# PowerBricksBoard1.net
KiCad netlist of a schematic drawn in EAGLE
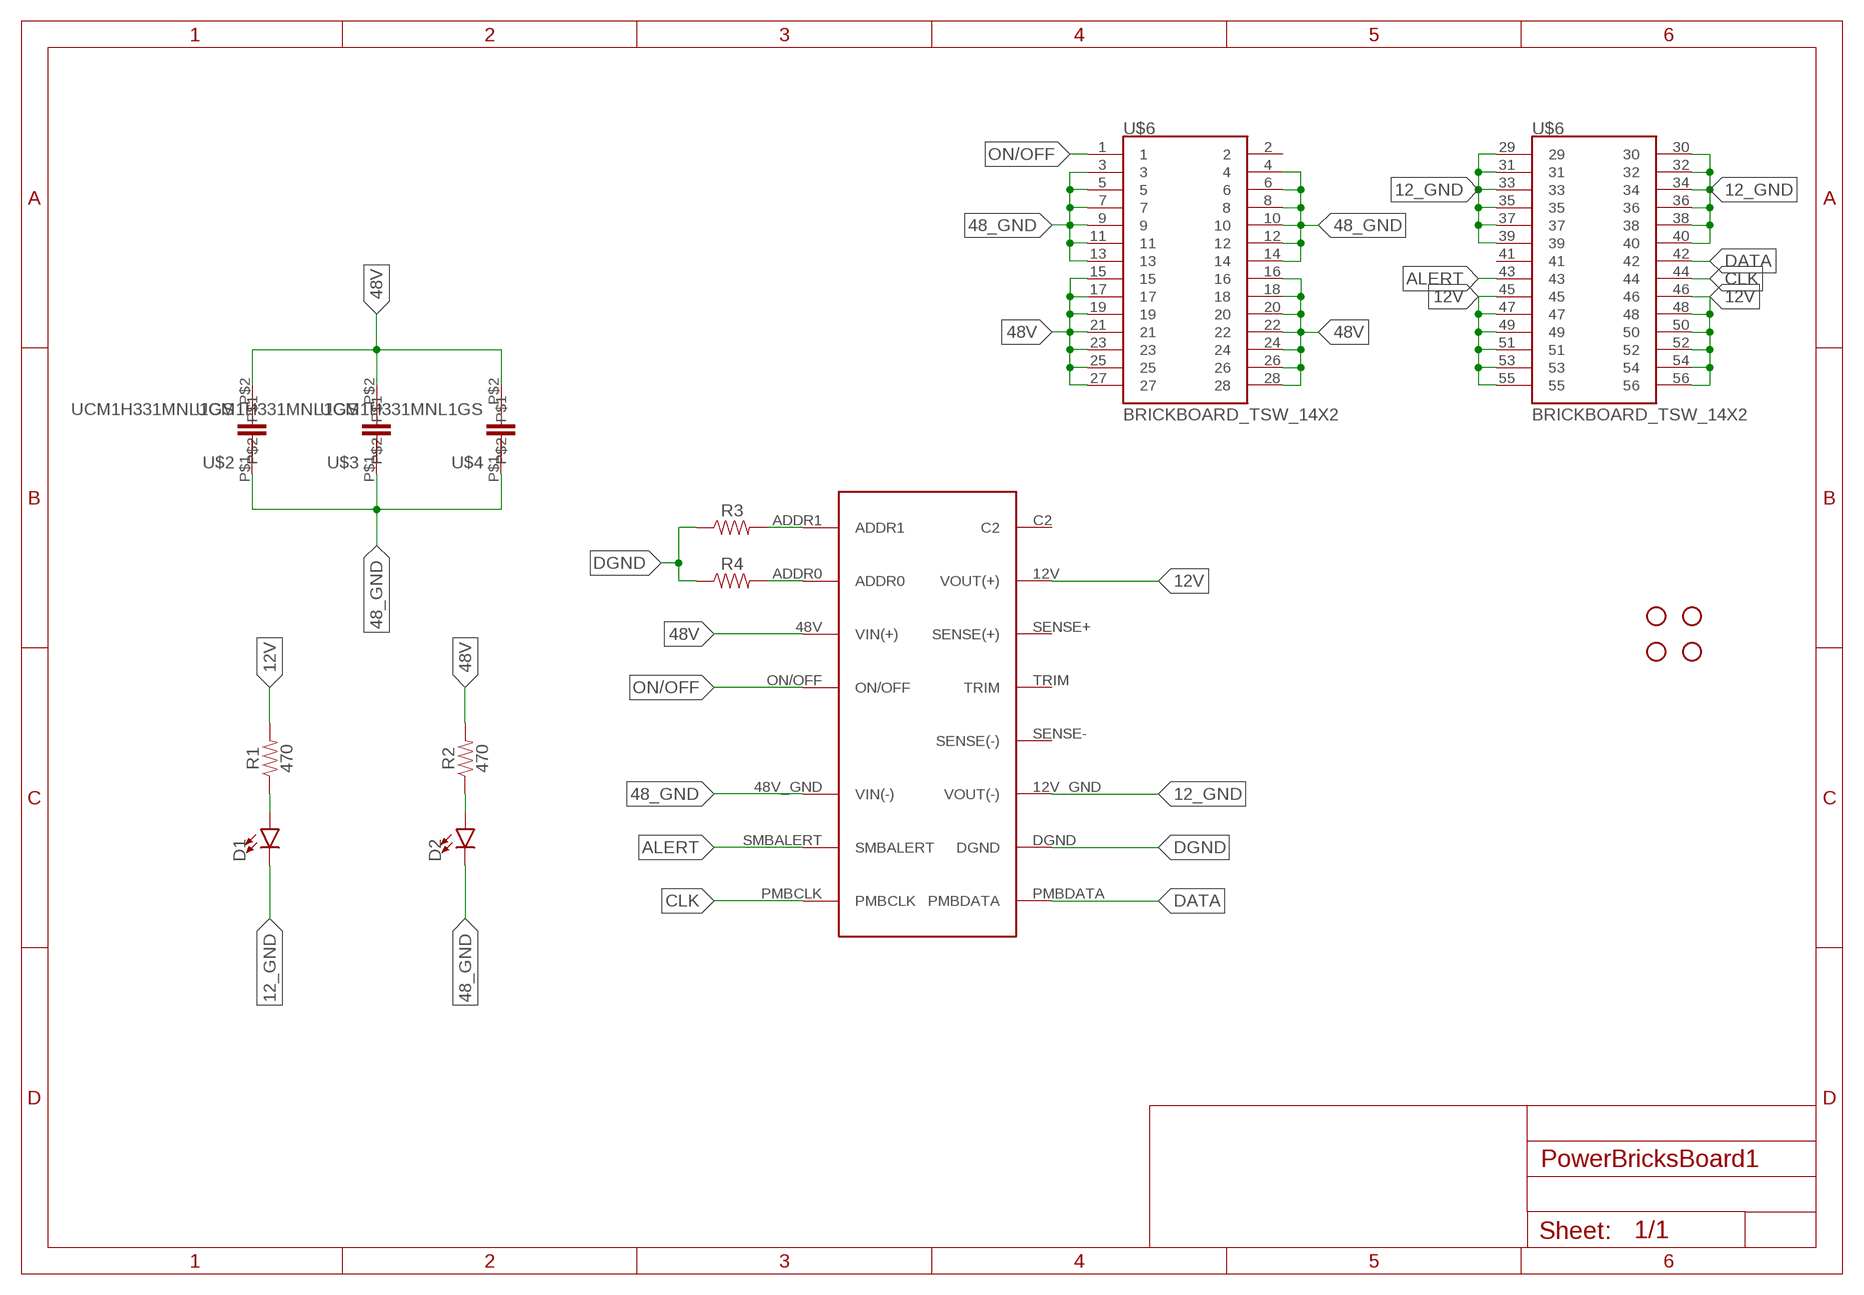
[diagram p0: schematic, sheet 1]

(export (version "E")
  (design (tool "Eeschema 10.0.6"))
  (components
    (comp (ref "D1")
      (value "LED0603")
      (footprint "eagle-import:LED-0603")
      (libsource (lib "eagle-import") (part "LED0603"))
    )
    (comp (ref "D2")
      (value "LED0603")
      (footprint "eagle-import:LED-0603")
      (libsource (lib "eagle-import") (part "LED0603"))
    )
    (comp (ref "H1")
      (value "STAND-OFF")
      (footprint "eagle-import:STAND-OFF")
      (libsource (lib "eagle-import") (part "STAND-OFF"))
    )
    (comp (ref "H2")
      (value "STAND-OFF")
      (footprint "eagle-import:STAND-OFF")
      (libsource (lib "eagle-import") (part "STAND-OFF"))
    )
    (comp (ref "H3")
      (value "STAND-OFF")
      (footprint "eagle-import:STAND-OFF")
      (libsource (lib "eagle-import") (part "STAND-OFF"))
    )
    (comp (ref "H4")
      (value "STAND-OFF")
      (footprint "eagle-import:STAND-OFF")
      (libsource (lib "eagle-import") (part "STAND-OFF"))
    )
    (comp (ref "R1")
      (value "470")
      (footprint "eagle-import:0603")
      (libsource (lib "eagle-import") (part "RESISTOR0603"))
    )
    (comp (ref "R2")
      (value "470")
      (footprint "eagle-import:0603")
      (libsource (lib "eagle-import") (part "RESISTOR0603"))
    )
    (comp (ref "R3")
      (value "RESISTOR0603")
      (footprint "eagle-import:0603")
      (libsource (lib "eagle-import") (part "RESISTOR0603"))
    )
    (comp (ref "R4")
      (value "RESISTOR0603")
      (footprint "eagle-import:0603")
      (libsource (lib "eagle-import") (part "RESISTOR0603"))
    )
    (comp (ref "U$1")
      (value "Q48SC12050NRDH")
      (footprint "eagle-import:Q48SC12050NRDH")
      (libsource (lib "eagle-import") (part "Q48SC12050NRDH"))
    )
    (comp (ref "U$2")
      (value "UCM1H331MNL1GS")
      (footprint "eagle-import:UCM1H331MNL1GS")
      (libsource (lib "eagle-import") (part "UCM1H331MNL1GS"))
    )
    (comp (ref "U$3")
      (value "UCM1H331MNL1GS")
      (footprint "eagle-import:UCM1H331MNL1GS")
      (libsource (lib "eagle-import") (part "UCM1H331MNL1GS"))
    )
    (comp (ref "U$4")
      (value "UCM1H331MNL1GS")
      (footprint "eagle-import:UCM1H331MNL1GS")
      (libsource (lib "eagle-import") (part "UCM1H331MNL1GS"))
    )
    (comp (ref "U$6")
      (value "BRICKBOARD_TSW_14X2")
      (footprint "eagle-import:BRICKBOARD_TSW_14X2")
      (libsource (lib "eagle-import") (part "BRICKBOARD_TSW_14X2"))
    )
  )
  (nets
    (net (code "1") (name "12V") (class "Default")
      (node (ref "R1") (pin "2") (pinfunction "2_2") (pintype "passive"))
      (node (ref "U$1") (pin "12V") (pinfunction "VOUT(+)_12V") (pintype "bidirectional"))
      (node (ref "U$6") (pin "45") (pinfunction "45_45") (pintype "bidirectional"))
      (node (ref "U$6") (pin "46") (pinfunction "46_46") (pintype "bidirectional"))
      (node (ref "U$6") (pin "47") (pinfunction "47_47") (pintype "bidirectional"))
      (node (ref "U$6") (pin "48") (pinfunction "48_48") (pintype "bidirectional"))
      (node (ref "U$6") (pin "49") (pinfunction "49_49") (pintype "bidirectional"))
      (node (ref "U$6") (pin "50") (pinfunction "50_50") (pintype "bidirectional"))
      (node (ref "U$6") (pin "51") (pinfunction "51_51") (pintype "bidirectional"))
      (node (ref "U$6") (pin "52") (pinfunction "52_52") (pintype "bidirectional"))
      (node (ref "U$6") (pin "53") (pinfunction "53_53") (pintype "bidirectional"))
      (node (ref "U$6") (pin "54") (pinfunction "54_54") (pintype "bidirectional"))
      (node (ref "U$6") (pin "55") (pinfunction "55_55") (pintype "bidirectional"))
      (node (ref "U$6") (pin "56") (pinfunction "56_56") (pintype "bidirectional"))
    )
    (net (code "2") (name "12_GND") (class "Default")
      (node (ref "D1") (pin "C") (pinfunction "C_C") (pintype "passive"))
      (node (ref "U$1") (pin "12V_GND") (pinfunction "VOUT(-)_12V_GND") (pintype "bidirectional"))
      (node (ref "U$6") (pin "29") (pinfunction "29_29") (pintype "bidirectional"))
      (node (ref "U$6") (pin "30") (pinfunction "30_30") (pintype "bidirectional"))
      (node (ref "U$6") (pin "31") (pinfunction "31_31") (pintype "bidirectional"))
      (node (ref "U$6") (pin "32") (pinfunction "32_32") (pintype "bidirectional"))
      (node (ref "U$6") (pin "33") (pinfunction "33_33") (pintype "bidirectional"))
      (node (ref "U$6") (pin "34") (pinfunction "34_34") (pintype "bidirectional"))
      (node (ref "U$6") (pin "35") (pinfunction "35_35") (pintype "bidirectional"))
      (node (ref "U$6") (pin "36") (pinfunction "36_36") (pintype "bidirectional"))
      (node (ref "U$6") (pin "37") (pinfunction "37_37") (pintype "bidirectional"))
      (node (ref "U$6") (pin "38") (pinfunction "38_38") (pintype "bidirectional"))
      (node (ref "U$6") (pin "39") (pinfunction "39_39") (pintype "bidirectional"))
      (node (ref "U$6") (pin "40") (pinfunction "40_40") (pintype "bidirectional"))
    )
    (net (code "3") (name "48V") (class "Default")
      (node (ref "R2") (pin "2") (pinfunction "2_2") (pintype "passive"))
      (node (ref "U$1") (pin "48V") (pinfunction "VIN(+)_48V") (pintype "bidirectional"))
      (node (ref "U$2") (pin "P$2") (pinfunction "P$2_P$2") (pintype "bidirectional"))
      (node (ref "U$3") (pin "P$2") (pinfunction "P$2_P$2") (pintype "bidirectional"))
      (node (ref "U$4") (pin "P$2") (pinfunction "P$2_P$2") (pintype "bidirectional"))
      (node (ref "U$6") (pin "15") (pinfunction "15_15") (pintype "bidirectional"))
      (node (ref "U$6") (pin "16") (pinfunction "16_16") (pintype "bidirectional"))
      (node (ref "U$6") (pin "17") (pinfunction "17_17") (pintype "bidirectional"))
      (node (ref "U$6") (pin "18") (pinfunction "18_18") (pintype "bidirectional"))
      (node (ref "U$6") (pin "19") (pinfunction "19_19") (pintype "bidirectional"))
      (node (ref "U$6") (pin "20") (pinfunction "20_20") (pintype "bidirectional"))
      (node (ref "U$6") (pin "21") (pinfunction "21_21") (pintype "bidirectional"))
      (node (ref "U$6") (pin "22") (pinfunction "22_22") (pintype "bidirectional"))
      (node (ref "U$6") (pin "23") (pinfunction "23_23") (pintype "bidirectional"))
      (node (ref "U$6") (pin "24") (pinfunction "24_24") (pintype "bidirectional"))
      (node (ref "U$6") (pin "25") (pinfunction "25_25") (pintype "bidirectional"))
      (node (ref "U$6") (pin "26") (pinfunction "26_26") (pintype "bidirectional"))
      (node (ref "U$6") (pin "27") (pinfunction "27_27") (pintype "bidirectional"))
      (node (ref "U$6") (pin "28") (pinfunction "28_28") (pintype "bidirectional"))
    )
    (net (code "4") (name "48_GND") (class "Default")
      (node (ref "D2") (pin "C") (pinfunction "C_C") (pintype "passive"))
      (node (ref "U$1") (pin "48V_GND") (pinfunction "VIN(-)_48V_GND") (pintype "bidirectional"))
      (node (ref "U$2") (pin "P$1") (pinfunction "P$1_P$1") (pintype "bidirectional"))
      (node (ref "U$3") (pin "P$1") (pinfunction "P$1_P$1") (pintype "bidirectional"))
      (node (ref "U$4") (pin "P$1") (pinfunction "P$1_P$1") (pintype "bidirectional"))
      (node (ref "U$6") (pin "10") (pinfunction "10_10") (pintype "bidirectional"))
      (node (ref "U$6") (pin "11") (pinfunction "11_11") (pintype "bidirectional"))
      (node (ref "U$6") (pin "12") (pinfunction "12_12") (pintype "bidirectional"))
      (node (ref "U$6") (pin "13") (pinfunction "13_13") (pintype "bidirectional"))
      (node (ref "U$6") (pin "14") (pinfunction "14_14") (pintype "bidirectional"))
      (node (ref "U$6") (pin "3") (pinfunction "3_3") (pintype "bidirectional"))
      (node (ref "U$6") (pin "4") (pinfunction "4_4") (pintype "bidirectional"))
      (node (ref "U$6") (pin "5") (pinfunction "5_5") (pintype "bidirectional"))
      (node (ref "U$6") (pin "6") (pinfunction "6_6") (pintype "bidirectional"))
      (node (ref "U$6") (pin "7") (pinfunction "7_7") (pintype "bidirectional"))
      (node (ref "U$6") (pin "8") (pinfunction "8_8") (pintype "bidirectional"))
      (node (ref "U$6") (pin "9") (pinfunction "9_9") (pintype "bidirectional"))
    )
    (net (code "5") (name "ALERT") (class "Default")
      (node (ref "U$1") (pin "SMBALERT") (pinfunction "SMBALERT_SMBALERT") (pintype "bidirectional"))
      (node (ref "U$6") (pin "43") (pinfunction "43_43") (pintype "bidirectional"))
    )
    (net (code "6") (name "CLK") (class "Default")
      (node (ref "U$1") (pin "PMBCLK") (pinfunction "PMBCLK_PMBCLK") (pintype "bidirectional"))
      (node (ref "U$6") (pin "44") (pinfunction "44_44") (pintype "bidirectional"))
    )
    (net (code "7") (name "DATA") (class "Default")
      (node (ref "U$1") (pin "PMBDATA") (pinfunction "PMBDATA_PMBDATA") (pintype "bidirectional"))
      (node (ref "U$6") (pin "42") (pinfunction "42_42") (pintype "bidirectional"))
    )
    (net (code "8") (name "DGND") (class "Default")
      (node (ref "R3") (pin "1") (pinfunction "1_1") (pintype "passive"))
      (node (ref "R4") (pin "1") (pinfunction "1_1") (pintype "passive"))
      (node (ref "U$1") (pin "DGND") (pinfunction "DGND_DGND") (pintype "bidirectional"))
    )
    (net (code "9") (name "Net-(D1-PadA)") (class "Default")
      (node (ref "D1") (pin "A") (pinfunction "A_A") (pintype "passive"))
      (node (ref "R1") (pin "1") (pinfunction "1_1") (pintype "passive"))
    )
    (net (code "10") (name "Net-(D2-PadA)") (class "Default")
      (node (ref "D2") (pin "A") (pinfunction "A_A") (pintype "passive"))
      (node (ref "R2") (pin "1") (pinfunction "1_1") (pintype "passive"))
    )
    (net (code "11") (name "Net-(R3-Pad2)") (class "Default")
      (node (ref "R3") (pin "2") (pinfunction "2_2") (pintype "passive"))
      (node (ref "U$1") (pin "ADDR1") (pinfunction "ADDR1_ADDR1") (pintype "bidirectional"))
    )
    (net (code "12") (name "Net-(R4-Pad2)") (class "Default")
      (node (ref "R4") (pin "2") (pinfunction "2_2") (pintype "passive"))
      (node (ref "U$1") (pin "ADDR0") (pinfunction "ADDR0_ADDR0") (pintype "bidirectional"))
    )
    (net (code "13") (name "ON{slash}OFF") (class "Default")
      (node (ref "U$1") (pin "ON/OFF") (pinfunction "ON/OFF_ON/OFF") (pintype "bidirectional"))
      (node (ref "U$6") (pin "1") (pinfunction "1_1") (pintype "bidirectional"))
    )
    (net (code "14") (name "unconnected-(U$1-PadC2)") (class "Default")
      (node (ref "U$1") (pin "C2") (pinfunction "C2_C2") (pintype "bidirectional"))
    )
    (net (code "15") (name "unconnected-(U$1-PadTRIM)") (class "Default")
      (node (ref "U$1") (pin "TRIM") (pinfunction "TRIM_TRIM") (pintype "bidirectional"))
    )
    (net (code "16") (name "unconnected-(U$1-SENSE(+)-PadSENSE+)") (class "Default")
      (node (ref "U$1") (pin "SENSE+") (pinfunction "SENSE(+)_SENSE+") (pintype "bidirectional"))
    )
    (net (code "17") (name "unconnected-(U$1-SENSE(-)-PadSENSE-)") (class "Default")
      (node (ref "U$1") (pin "SENSE-") (pinfunction "SENSE(-)_SENSE-") (pintype "bidirectional"))
    )
    (net (code "18") (name "unconnected-(U$6-Pad2)") (class "Default")
      (node (ref "U$6") (pin "2") (pinfunction "2_2") (pintype "bidirectional"))
    )
    (net (code "19") (name "unconnected-(U$6-Pad41)") (class "Default")
      (node (ref "U$6") (pin "41") (pinfunction "41_41") (pintype "bidirectional"))
    )
  )
)
